# S3C.net
KiCad netlist of a schematic drawn in Altium Designer
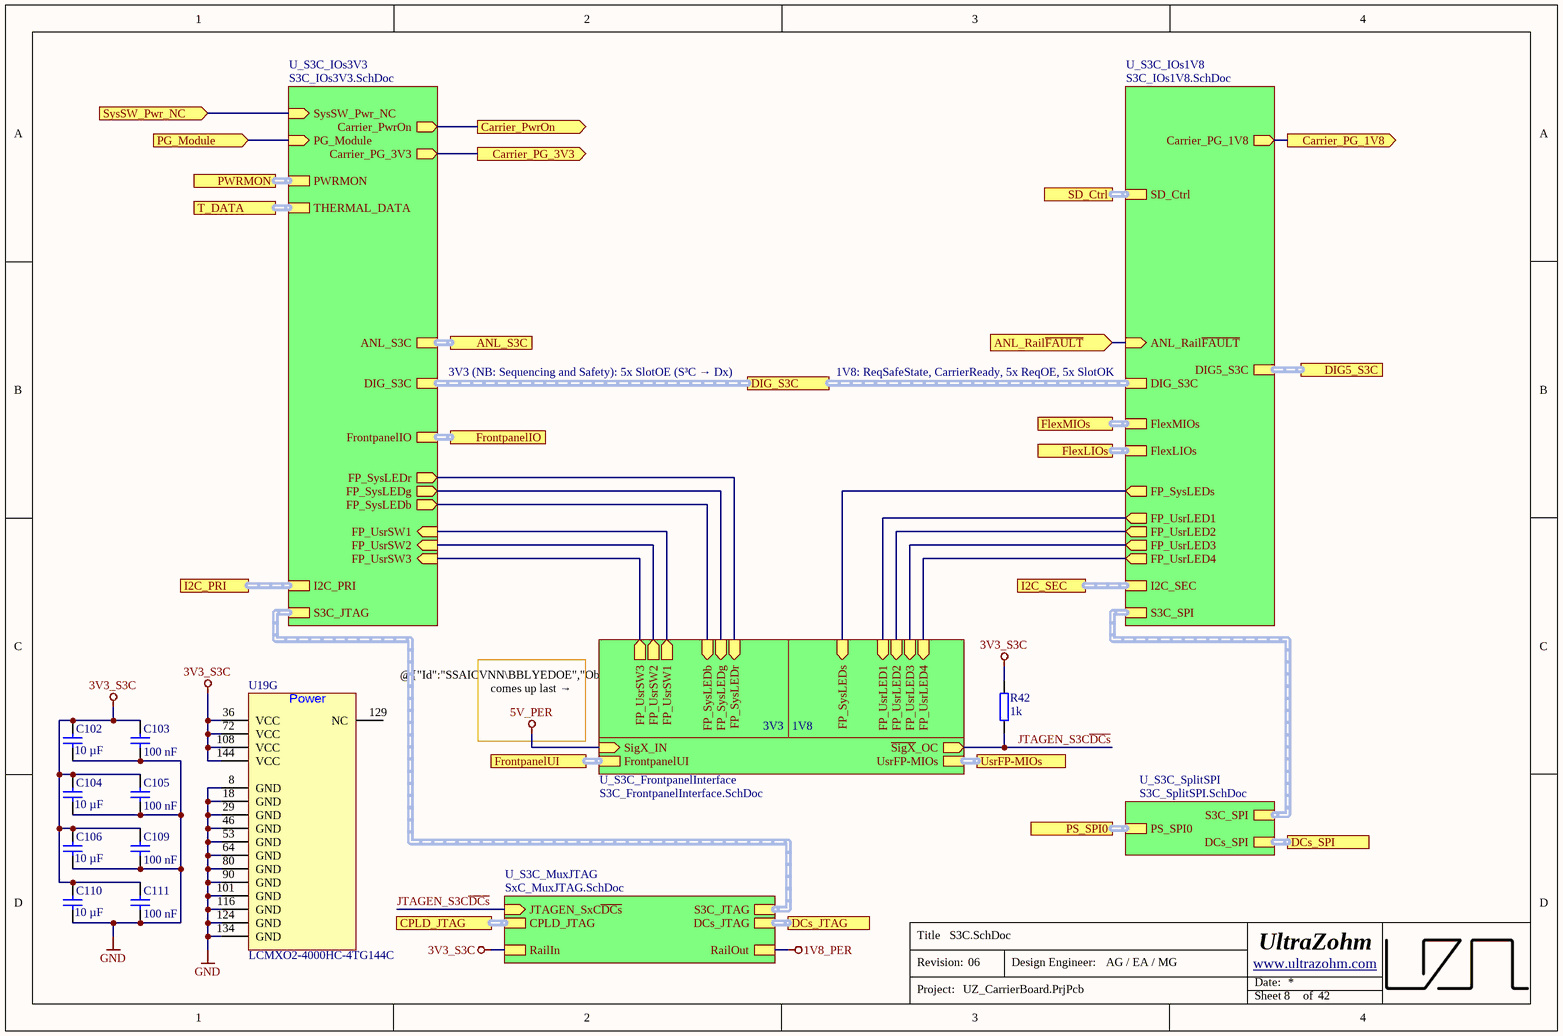
[diagram p0: S3C.SchDoc]

(export (version "E")
  (design (tool "Eeschema 10.0.6"))
  (components
    (comp (ref "C102")
      (value "10 µF")
      (footprint "C_0603_TE")
      (description "Generic capacitor")
      (fields
        (field (name "MANUFACTURER PART NUMBER") "UZgen_C_0603_10uF_6.3V_X7R")
        (field (name "MANUFACTURER") "UZgen")
        (field (name "CREATED FROM") "UZgenTool")
      )
      (libsource (lib "user") (part "CAP-NP"))
    )
    (comp (ref "C103")
      (value "100 nF")
      (footprint "C_0603_TE")
      (description "Generic capacitor")
      (fields
        (field (name "TOLERANCE") "10 %")
        (field (name "VOLTAGE") "50 V")
        (field (name "CREATED FROM") "AGeiger")
      )
      (libsource (lib "user") (part "CAP-NP"))
    )
    (comp (ref "C104")
      (value "10 µF")
      (footprint "C_0603_TE")
      (description "Generic capacitor")
      (fields
        (field (name "MANUFACTURER PART NUMBER") "UZgen_C_0603_10uF_6.3V_X7R")
        (field (name "MANUFACTURER") "UZgen")
        (field (name "CREATED FROM") "UZgenTool")
      )
      (libsource (lib "user") (part "CAP-NP"))
    )
    (comp (ref "C105")
      (value "100 nF")
      (footprint "C_0603_TE")
      (description "Generic capacitor")
      (fields
        (field (name "TOLERANCE") "10 %")
        (field (name "VOLTAGE") "50 V")
        (field (name "CREATED FROM") "AGeiger")
      )
      (libsource (lib "user") (part "CAP-NP"))
    )
    (comp (ref "C106")
      (value "10 µF")
      (footprint "C_0603_TE")
      (description "Generic capacitor")
      (fields
        (field (name "MANUFACTURER PART NUMBER") "UZgen_C_0603_10uF_6.3V_X7R")
        (field (name "MANUFACTURER") "UZgen")
        (field (name "CREATED FROM") "UZgenTool")
      )
      (libsource (lib "user") (part "CAP-NP"))
    )
    (comp (ref "C109")
      (value "100 nF")
      (footprint "C_0603_TE")
      (description "Generic capacitor")
      (fields
        (field (name "TOLERANCE") "10 %")
        (field (name "VOLTAGE") "50 V")
        (field (name "CREATED FROM") "AGeiger")
      )
      (libsource (lib "user") (part "CAP-NP"))
    )
    (comp (ref "C110")
      (value "10 µF")
      (footprint "C_0603_TE")
      (description "Generic capacitor")
      (fields
        (field (name "MANUFACTURER PART NUMBER") "UZgen_C_0603_10uF_6.3V_X7R")
        (field (name "MANUFACTURER") "UZgen")
        (field (name "CREATED FROM") "UZgenTool")
      )
      (libsource (lib "user") (part "CAP-NP"))
    )
    (comp (ref "C111")
      (value "100 nF")
      (footprint "C_0603_TE")
      (description "Generic capacitor")
      (fields
        (field (name "TOLERANCE") "10 %")
        (field (name "VOLTAGE") "50 V")
        (field (name "CREATED FROM") "AGeiger")
      )
      (libsource (lib "user") (part "CAP-NP"))
    )
    (comp (ref "R42")
      (value "1k")
      (footprint "R_0603_TE")
      (description "Generic resistor")
      (fields
        (field (name "MANUFACTURER PART NUMBER") "UZgen_R_0603_1k")
        (field (name "MANUFACTURER") "UZgen")
        (field (name "CREATED FROM") "UZgenTool")
      )
      (libsource (lib "user") (part "RES"))
    )
    (comp (ref "U19")
      (value "LCMXO2-4000HC-4TG144C")
      (footprint "QFP50P2200X2200X160-144N")
      (description "TQFP-144(20x20) Programmable Logic Device (CPLDs/FPGAs) ROHS")
      (fields
        (field (name "MANUFACTURER") "Lattice")
        (field (name "LCSC PART NUMBER") "C1521625")
        (field (name "CREATED FROM") "FRosner")
      )
      (libsource (lib "user") (part "LCMXO2-4000"))
    )
  )
  (nets
    (net (code "45") (name "/JTAGEN_S3C~{DCs}") (class "Default")
      (node (ref "R42") (pin "1") (pinfunction "1_1") (pintype "passive"))
    )
    (net (code "56") (name "3V3_S3C") (class "Default")
      (node (ref "C102") (pin "1") (pinfunction "1_1") (pintype "passive"))
      (node (ref "C103") (pin "2") (pinfunction "2_2") (pintype "passive"))
      (node (ref "C104") (pin "1") (pinfunction "1_1") (pintype "passive"))
      (node (ref "C105") (pin "2") (pinfunction "2_2") (pintype "passive"))
      (node (ref "C106") (pin "1") (pinfunction "1_1") (pintype "passive"))
      (node (ref "C109") (pin "2") (pinfunction "2_2") (pintype "passive"))
      (node (ref "C110") (pin "1") (pinfunction "1_1") (pintype "passive"))
      (node (ref "C111") (pin "2") (pinfunction "2_2") (pintype "passive"))
      (node (ref "R42") (pin "2") (pinfunction "2_2") (pintype "passive"))
      (node (ref "U19") (pin "108") (pinfunction "VCC_108") (pintype "power_in"))
      (node (ref "U19") (pin "144") (pinfunction "VCC_144") (pintype "power_in"))
      (node (ref "U19") (pin "36") (pinfunction "VCC_36") (pintype "power_in"))
      (node (ref "U19") (pin "72") (pinfunction "VCC_72") (pintype "power_in"))
    )
    (net (code "58") (name "GND") (class "Default")
      (node (ref "C102") (pin "2") (pinfunction "2_2") (pintype "passive"))
      (node (ref "C103") (pin "1") (pinfunction "1_1") (pintype "passive"))
      (node (ref "C104") (pin "2") (pinfunction "2_2") (pintype "passive"))
      (node (ref "C105") (pin "1") (pinfunction "1_1") (pintype "passive"))
      (node (ref "C106") (pin "2") (pinfunction "2_2") (pintype "passive"))
      (node (ref "C109") (pin "1") (pinfunction "1_1") (pintype "passive"))
      (node (ref "C110") (pin "2") (pinfunction "2_2") (pintype "passive"))
      (node (ref "C111") (pin "1") (pinfunction "1_1") (pintype "passive"))
      (node (ref "U19") (pin "101") (pinfunction "GND_101") (pintype "power_in"))
      (node (ref "U19") (pin "116") (pinfunction "GND_116") (pintype "power_in"))
      (node (ref "U19") (pin "124") (pinfunction "GND_124") (pintype "power_in"))
      (node (ref "U19") (pin "134") (pinfunction "GND_134") (pintype "power_in"))
      (node (ref "U19") (pin "18") (pinfunction "GND_18") (pintype "power_in"))
      (node (ref "U19") (pin "29") (pinfunction "GND_29") (pintype "power_in"))
      (node (ref "U19") (pin "46") (pinfunction "GND_46") (pintype "power_in"))
      (node (ref "U19") (pin "53") (pinfunction "GND_53") (pintype "power_in"))
      (node (ref "U19") (pin "64") (pinfunction "GND_64") (pintype "power_in"))
      (node (ref "U19") (pin "8") (pinfunction "GND_8") (pintype "power_in"))
      (node (ref "U19") (pin "80") (pinfunction "GND_80") (pintype "power_in"))
      (node (ref "U19") (pin "90") (pinfunction "GND_90") (pintype "power_in"))
    )
    (net (code "59") (name "unconnected-(U19G-NC-Pad129)") (class "Default")
      (node (ref "U19") (pin "129") (pinfunction "NC_129") (pintype "passive"))
    )
  )
)
